# FPGA_Configuration.net
KiCad netlist of a schematic drawn in Altium Designer
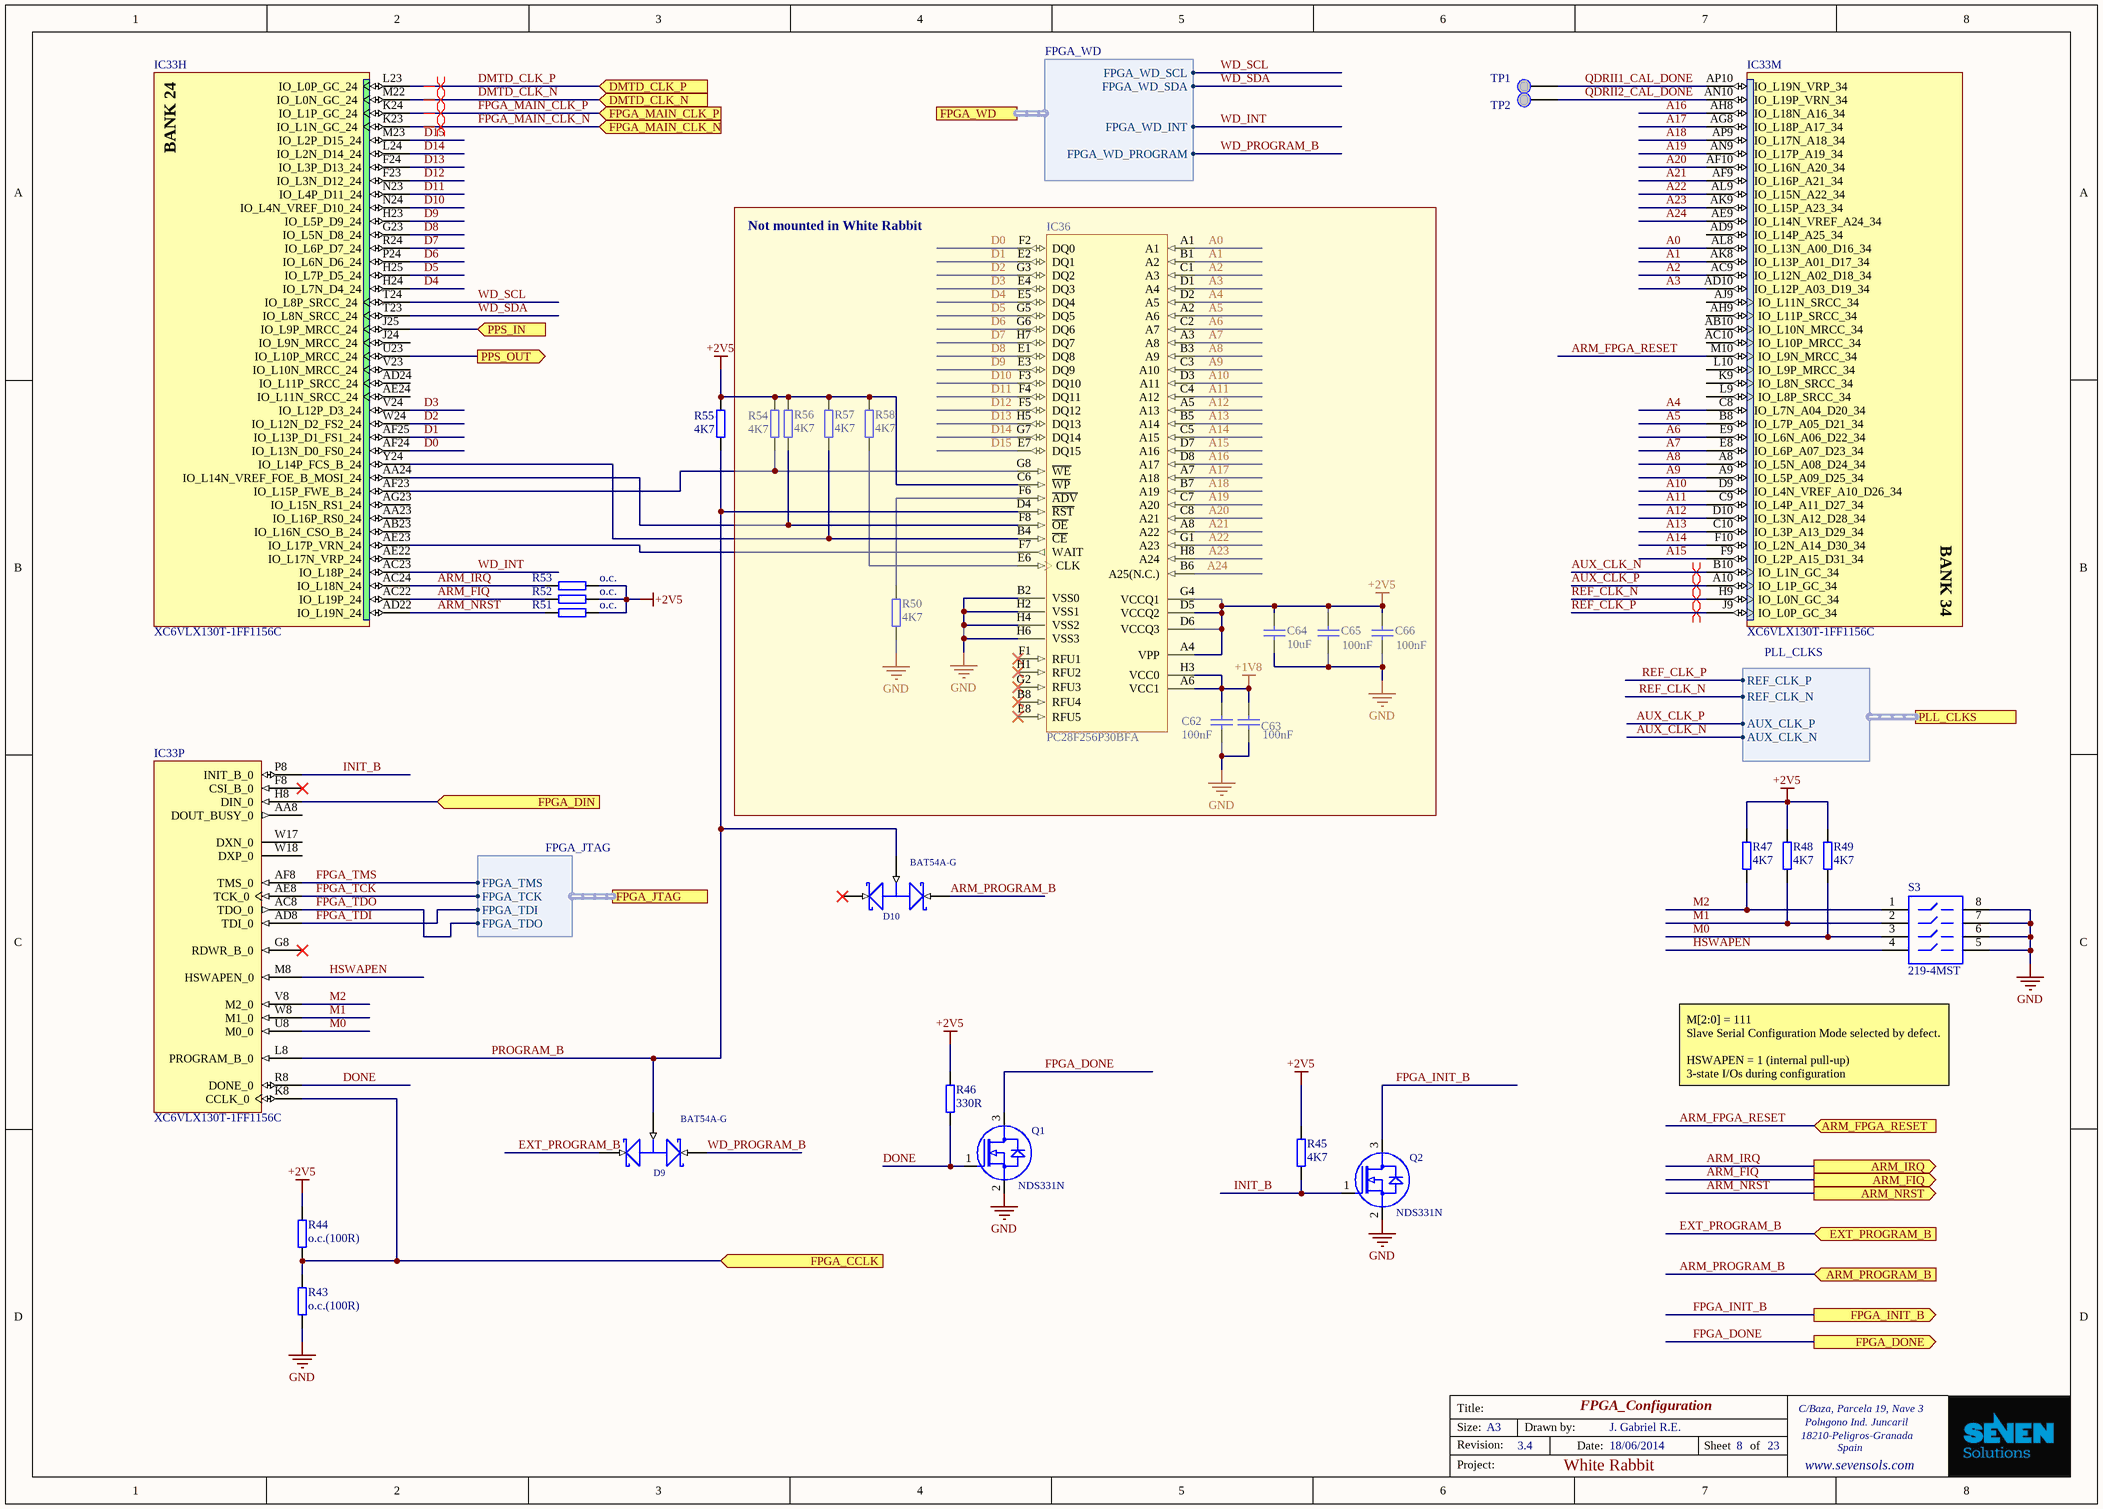
[diagram p0: FPGA_Configuration.SchDoc]

(export (version "E")
  (design (tool "Eeschema 10.0.6"))
  (components
    (comp (ref "C62")
      (value "100nF")
      (footprint "CC1005-0402")
      (description "Capacitor")
      (fields
        (field (name "TOLERANCE") "±10%")
        (field (name "VOLTAGE") "16V")
        (field (name "PUBLISHER") "Altium Limited")
      )
      (libsource (lib "wr_switch") (part "Cap"))
    )
    (comp (ref "C63")
      (value "100nF")
      (footprint "CC1005-0402")
      (description "Capacitor")
      (fields
        (field (name "TOLERANCE") "±10%")
        (field (name "VOLTAGE") "16V")
        (field (name "PUBLISHER") "Altium Limited")
      )
      (libsource (lib "wr_switch") (part "Cap"))
    )
    (comp (ref "C64")
      (value "10uF")
      (footprint "CC1608-0603")
      (description "Capacitor")
      (fields
        (field (name "TOLERANCE") "±20%")
        (field (name "VOLTAGE") "6.3V")
        (field (name "PUBLISHER") "Altium Limited")
      )
      (libsource (lib "wr_switch") (part "Cap"))
    )
    (comp (ref "C65")
      (value "100nF")
      (footprint "CC1005-0402")
      (description "Capacitor")
      (fields
        (field (name "TOLERANCE") "±10%")
        (field (name "VOLTAGE") "16V")
        (field (name "PUBLISHER") "Altium Limited")
      )
      (libsource (lib "wr_switch") (part "Cap"))
    )
    (comp (ref "C66")
      (value "100nF")
      (footprint "CC1005-0402")
      (description "Capacitor")
      (fields
        (field (name "TOLERANCE") "±10%")
        (field (name "VOLTAGE") "16V")
        (field (name "PUBLISHER") "Altium Limited")
      )
      (libsource (lib "wr_switch") (part "Cap"))
    )
    (comp (ref "D9")
      (value "BAT54A-G")
      (footprint "SOT23")
      (description "Schottky Barrier Double Diode")
      (fields (field (name "PUBLISHER") "Altium Limited"))
      (libsource (lib "wr_switch") (part "BAT54A.1"))
    )
    (comp (ref "D10")
      (value "BAT54A-G")
      (footprint "SOT23")
      (description "Schottky Barrier Double Diode")
      (fields (field (name "PUBLISHER") "Altium Limited"))
      (libsource (lib "wr_switch") (part "BAT54A.1"))
    )
    (comp (ref "IC33")
      (value "XC6VLX130T-1FF1156C")
      (footprint "FF1156")
      (fields (field (name "PUBLISHER") "Altium Limited"))
      (libsource (lib "") (part "XC6VLX130T-1FF1156C_1"))
    )
    (comp (ref "IC36")
      (value "PC28F256P30BFA")
      (footprint "BGA64C100P8X8_1300X1000X120")
      (description "NOR Flash Memory, 256Mbit")
      (libsource (lib "wr_switch") (part "PC28F256P30BFA"))
    )
    (comp (ref "Q1")
      (value "NDS331N")
      (footprint "SOT23-3")
      (description "N-Channel Logic Level Enhancement Mode Field Effect Transistor")
      (libsource (lib "wr_switch") (part "NDS331N"))
    )
    (comp (ref "Q2")
      (value "NDS331N")
      (footprint "SOT23-3")
      (description "N-Channel Logic Level Enhancement Mode Field Effect Transistor")
      (libsource (lib "wr_switch") (part "NDS331N"))
    )
    (comp (ref "R43")
      (value "o.c.(100R)")
      (footprint "0402")
      (description "SMD Resistor")
      (fields (field (name "TOLERANCE") "±1%") (field (name "Comment") "100R(o.c.)"))
      (libsource (lib "wr_switch") (part "RES_SMD"))
    )
    (comp (ref "R44")
      (value "o.c.(100R)")
      (footprint "0402")
      (description "SMD Resistor")
      (fields (field (name "TOLERANCE") "±1%") (field (name "Comment") "100R(o.c.)"))
      (libsource (lib "wr_switch") (part "RES_SMD"))
    )
    (comp (ref "R45")
      (value "4K7")
      (footprint "0402")
      (description "SMD Resistor")
      (fields (field (name "TOLERANCE") "±1%"))
      (libsource (lib "wr_switch") (part "RES_SMD"))
    )
    (comp (ref "R46")
      (value "330R")
      (footprint "0402")
      (description "SMD Resistor")
      (fields (field (name "TOLERANCE") "±1%"))
      (libsource (lib "wr_switch") (part "RES_SMD"))
    )
    (comp (ref "R47")
      (value "4K7")
      (footprint "0402")
      (description "SMD Resistor")
      (fields (field (name "TOLERANCE") "±1%"))
      (libsource (lib "wr_switch") (part "RES_SMD"))
    )
    (comp (ref "R48")
      (value "4K7")
      (footprint "0402")
      (description "SMD Resistor")
      (fields (field (name "TOLERANCE") "±1%"))
      (libsource (lib "wr_switch") (part "RES_SMD"))
    )
    (comp (ref "R49")
      (value "4K7")
      (footprint "0402")
      (description "SMD Resistor")
      (fields (field (name "TOLERANCE") "±1%"))
      (libsource (lib "wr_switch") (part "RES_SMD"))
    )
    (comp (ref "R50")
      (value "4K7")
      (footprint "0402")
      (description "SMD Resistor")
      (fields (field (name "TOLERANCE") "±1%"))
      (libsource (lib "wr_switch") (part "RES_SMD"))
    )
    (comp (ref "R51")
      (value "o.c.")
      (footprint "0402")
      (description "SMD Resistor")
      (libsource (lib "wr_switch") (part "RES_SMD"))
    )
    (comp (ref "R52")
      (value "o.c.")
      (footprint "0402")
      (description "SMD Resistor")
      (libsource (lib "wr_switch") (part "RES_SMD"))
    )
    (comp (ref "R53")
      (value "o.c.")
      (footprint "0402")
      (description "SMD Resistor")
      (libsource (lib "wr_switch") (part "RES_SMD"))
    )
    (comp (ref "R54")
      (value "4K7")
      (footprint "0402")
      (description "SMD Resistor")
      (fields (field (name "TOLERANCE") "±1%"))
      (libsource (lib "wr_switch") (part "RES_SMD"))
    )
    (comp (ref "R55")
      (value "4K7")
      (footprint "0402")
      (description "SMD Resistor")
      (fields (field (name "TOLERANCE") "±1%"))
      (libsource (lib "wr_switch") (part "RES_SMD"))
    )
    (comp (ref "R56")
      (value "4K7")
      (footprint "0402")
      (description "SMD Resistor")
      (fields (field (name "TOLERANCE") "±1%"))
      (libsource (lib "wr_switch") (part "RES_SMD"))
    )
    (comp (ref "R57")
      (value "4K7")
      (footprint "0402")
      (description "SMD Resistor")
      (fields (field (name "TOLERANCE") "±1%"))
      (libsource (lib "wr_switch") (part "RES_SMD"))
    )
    (comp (ref "R58")
      (value "4K7")
      (footprint "0402")
      (description "SMD Resistor")
      (fields (field (name "TOLERANCE") "±1%"))
      (libsource (lib "wr_switch") (part "RES_SMD"))
    )
    (comp (ref "S3")
      (value "219-4MST")
      (footprint "7S_WR:NHDS-8")
      (description "4 Positions DIP SWITCH")
      (fields (field (name "MANUFACTURER") "CTS Electrocomponents"))
      (libsource (lib "wr_switch") (part "SW-DIP4"))
    )
    (comp (ref "TP1")
      (value "Test Point")
      (footprint "TEST_PAD_1mm")
      (description "SMD 1mm Test Point")
      (libsource (lib "wr_switch") (part "TEST_POINT"))
    )
    (comp (ref "TP2")
      (value "Test Point")
      (footprint "TEST_PAD_1mm")
      (description "SMD 1mm Test Point")
      (libsource (lib "wr_switch") (part "TEST_POINT"))
    )
  )
  (nets
    (net (code "4") (name "+1V8") (class "Default")
      (node (ref "C62") (pin "2") (pinfunction "2_2") (pintype "passive"))
      (node (ref "C63") (pin "2") (pinfunction "2_2") (pintype "passive"))
      (node (ref "IC36") (pin "A6") (pinfunction "VCC1_A6") (pintype "power_in"))
      (node (ref "IC36") (pin "H3") (pinfunction "VCC0_H3") (pintype "power_in"))
    )
    (net (code "5") (name "+2V5") (class "Default")
      (node (ref "C64") (pin "2") (pinfunction "2_2") (pintype "passive"))
      (node (ref "C65") (pin "2") (pinfunction "2_2") (pintype "passive"))
      (node (ref "C66") (pin "2") (pinfunction "2_2") (pintype "passive"))
      (node (ref "IC36") (pin "A4") (pinfunction "VPP_A4") (pintype "passive"))
      (node (ref "IC36") (pin "C6") (pinfunction "~{WP}_C6") (pintype "input"))
      (node (ref "IC36") (pin "D5") (pinfunction "VCCQ2_D5") (pintype "power_in"))
      (node (ref "IC36") (pin "D6") (pinfunction "VCCQ3_D6") (pintype "power_in"))
      (node (ref "IC36") (pin "G4") (pinfunction "VCCQ1_G4") (pintype "power_in"))
      (node (ref "R44") (pin "2") (pinfunction "2_2") (pintype "passive"))
      (node (ref "R45") (pin "1") (pinfunction "1_1") (pintype "passive"))
      (node (ref "R46") (pin "2") (pinfunction "2_2") (pintype "passive"))
      (node (ref "R47") (pin "2") (pinfunction "2_2") (pintype "passive"))
      (node (ref "R48") (pin "2") (pinfunction "2_2") (pintype "passive"))
      (node (ref "R49") (pin "2") (pinfunction "2_2") (pintype "passive"))
      (node (ref "R51") (pin "1") (pinfunction "1_1") (pintype "passive"))
      (node (ref "R52") (pin "1") (pinfunction "1_1") (pintype "passive"))
      (node (ref "R53") (pin "1") (pinfunction "1_1") (pintype "passive"))
      (node (ref "R54") (pin "2") (pinfunction "2_2") (pintype "passive"))
      (node (ref "R55") (pin "2") (pinfunction "2_2") (pintype "passive"))
      (node (ref "R56") (pin "2") (pinfunction "2_2") (pintype "passive"))
      (node (ref "R57") (pin "2") (pinfunction "2_2") (pintype "passive"))
      (node (ref "R58") (pin "2") (pinfunction "2_2") (pintype "passive"))
    )
    (net (code "6") (name "/A0") (class "Default")
      (node (ref "IC33") (pin "AL8") (pinfunction "IO_L13N_A00_D16_34_AL8") (pintype "bidirectional"))
      (node (ref "IC36") (pin "A1") (pinfunction "A1_A1") (pintype "input"))
    )
    (net (code "7") (name "/A1") (class "Default")
      (node (ref "IC33") (pin "AK8") (pinfunction "IO_L13P_A01_D17_34_AK8") (pintype "bidirectional"))
      (node (ref "IC36") (pin "B1") (pinfunction "A2_B1") (pintype "input"))
    )
    (net (code "8") (name "/A2") (class "Default")
      (node (ref "IC33") (pin "AC9") (pinfunction "IO_L12N_A02_D18_34_AC9") (pintype "bidirectional"))
      (node (ref "IC36") (pin "C1") (pinfunction "A3_C1") (pintype "input"))
    )
    (net (code "9") (name "/A3") (class "Default")
      (node (ref "IC33") (pin "AD10") (pinfunction "IO_L12P_A03_D19_34_AD10") (pintype "bidirectional"))
      (node (ref "IC36") (pin "D1") (pinfunction "A4_D1") (pintype "input"))
    )
    (net (code "10") (name "/A4") (class "Default")
      (node (ref "IC33") (pin "C8") (pinfunction "IO_L7N_A04_D20_34_C8") (pintype "bidirectional"))
      (node (ref "IC36") (pin "D2") (pinfunction "A5_D2") (pintype "input"))
    )
    (net (code "11") (name "/A5") (class "Default")
      (node (ref "IC33") (pin "B8") (pinfunction "IO_L7P_A05_D21_34_B8") (pintype "bidirectional"))
      (node (ref "IC36") (pin "A2") (pinfunction "A6_A2") (pintype "input"))
    )
    (net (code "12") (name "/A6") (class "Default")
      (node (ref "IC33") (pin "E9") (pinfunction "IO_L6N_A06_D22_34_E9") (pintype "bidirectional"))
      (node (ref "IC36") (pin "C2") (pinfunction "A7_C2") (pintype "input"))
    )
    (net (code "13") (name "/A7") (class "Default")
      (node (ref "IC33") (pin "E8") (pinfunction "IO_L6P_A07_D23_34_E8") (pintype "bidirectional"))
      (node (ref "IC36") (pin "A3") (pinfunction "A8_A3") (pintype "input"))
    )
    (net (code "14") (name "/A8") (class "Default")
      (node (ref "IC33") (pin "A8") (pinfunction "IO_L5N_A08_D24_34_A8") (pintype "bidirectional"))
      (node (ref "IC36") (pin "B3") (pinfunction "A9_B3") (pintype "input"))
    )
    (net (code "15") (name "/A9") (class "Default")
      (node (ref "IC33") (pin "A9") (pinfunction "IO_L5P_A09_D25_34_A9") (pintype "bidirectional"))
      (node (ref "IC36") (pin "C3") (pinfunction "A10_C3") (pintype "input"))
    )
    (net (code "16") (name "/A10") (class "Default")
      (node (ref "IC33") (pin "D9") (pinfunction "IO_L4N_VREF_A10_D26_34_D9") (pintype "bidirectional"))
      (node (ref "IC36") (pin "D3") (pinfunction "A11_D3") (pintype "input"))
    )
    (net (code "17") (name "/A11") (class "Default")
      (node (ref "IC33") (pin "C9") (pinfunction "IO_L4P_A11_D27_34_C9") (pintype "bidirectional"))
      (node (ref "IC36") (pin "C4") (pinfunction "A12_C4") (pintype "input"))
    )
    (net (code "18") (name "/A12") (class "Default")
      (node (ref "IC33") (pin "D10") (pinfunction "IO_L3N_A12_D28_34_D10") (pintype "bidirectional"))
      (node (ref "IC36") (pin "A5") (pinfunction "A13_A5") (pintype "input"))
    )
    (net (code "19") (name "/A13") (class "Default")
      (node (ref "IC33") (pin "C10") (pinfunction "IO_L3P_A13_D29_34_C10") (pintype "bidirectional"))
      (node (ref "IC36") (pin "B5") (pinfunction "A14_B5") (pintype "input"))
    )
    (net (code "20") (name "/A14") (class "Default")
      (node (ref "IC33") (pin "F10") (pinfunction "IO_L2N_A14_D30_34_F10") (pintype "bidirectional"))
      (node (ref "IC36") (pin "C5") (pinfunction "A15_C5") (pintype "input"))
    )
    (net (code "21") (name "/A15") (class "Default")
      (node (ref "IC33") (pin "F9") (pinfunction "IO_L2P_A15_D31_34_F9") (pintype "bidirectional"))
      (node (ref "IC36") (pin "D7") (pinfunction "A16_D7") (pintype "input"))
    )
    (net (code "22") (name "/A16") (class "Default")
      (node (ref "IC33") (pin "AH8") (pinfunction "IO_L18N_A16_34_AH8") (pintype "bidirectional"))
      (node (ref "IC36") (pin "D8") (pinfunction "A17_D8") (pintype "input"))
    )
    (net (code "23") (name "/A17") (class "Default")
      (node (ref "IC33") (pin "AG8") (pinfunction "IO_L18P_A17_34_AG8") (pintype "bidirectional"))
      (node (ref "IC36") (pin "A7") (pinfunction "A18_A7") (pintype "input"))
    )
    (net (code "24") (name "/A18") (class "Default")
      (node (ref "IC33") (pin "AP9") (pinfunction "IO_L17N_A18_34_AP9") (pintype "bidirectional"))
      (node (ref "IC36") (pin "B7") (pinfunction "A19_B7") (pintype "input"))
    )
    (net (code "25") (name "/A19") (class "Default")
      (node (ref "IC33") (pin "AN9") (pinfunction "IO_L17P_A19_34_AN9") (pintype "bidirectional"))
      (node (ref "IC36") (pin "C7") (pinfunction "A20_C7") (pintype "input"))
    )
    (net (code "26") (name "/A20") (class "Default")
      (node (ref "IC33") (pin "AF10") (pinfunction "IO_L16N_A20_34_AF10") (pintype "bidirectional"))
      (node (ref "IC36") (pin "C8") (pinfunction "A21_C8") (pintype "input"))
    )
    (net (code "27") (name "/A21") (class "Default")
      (node (ref "IC33") (pin "AF9") (pinfunction "IO_L16P_A21_34_AF9") (pintype "bidirectional"))
      (node (ref "IC36") (pin "A8") (pinfunction "A22_A8") (pintype "input"))
    )
    (net (code "28") (name "/A22") (class "Default")
      (node (ref "IC33") (pin "AL9") (pinfunction "IO_L15N_A22_34_AL9") (pintype "bidirectional"))
      (node (ref "IC36") (pin "G1") (pinfunction "A23_G1") (pintype "input"))
    )
    (net (code "29") (name "/A23") (class "Default")
      (node (ref "IC33") (pin "AK9") (pinfunction "IO_L15P_A23_34_AK9") (pintype "bidirectional"))
      (node (ref "IC36") (pin "H8") (pinfunction "A24_H8") (pintype "input"))
    )
    (net (code "30") (name "/A24") (class "Default")
      (node (ref "IC33") (pin "AE9") (pinfunction "IO_L14N_VREF_A24_34_AE9") (pintype "bidirectional"))
      (node (ref "IC36") (pin "B6") (pinfunction "A25(N.C.)_B6") (pintype "input"))
    )
    (net (code "31") (name "/ARM_FIQ") (class "Default")
      (node (ref "IC33") (pin "AC22") (pinfunction "IO_L19P_24_AC22") (pintype "bidirectional"))
      (node (ref "R52") (pin "2") (pinfunction "2_2") (pintype "passive"))
    )
    (net (code "32") (name "/ARM_FPGA_RESET") (class "Default")
      (node (ref "IC33") (pin "M10") (pinfunction "IO_L9N_MRCC_34_M10") (pintype "bidirectional"))
    )
    (net (code "33") (name "/ARM_IRQ") (class "Default")
      (node (ref "IC33") (pin "AC24") (pinfunction "IO_L18N_24_AC24") (pintype "bidirectional"))
      (node (ref "R53") (pin "2") (pinfunction "2_2") (pintype "passive"))
    )
    (net (code "34") (name "/ARM_NRST") (class "Default")
      (node (ref "IC33") (pin "AD22") (pinfunction "IO_L19N_24_AD22") (pintype "bidirectional"))
      (node (ref "R51") (pin "2") (pinfunction "2_2") (pintype "passive"))
    )
    (net (code "35") (name "/ARM_PROGRAM_B") (class "Default")
      (node (ref "D10") (pin "2") (pinfunction "K2_2") (pintype "input"))
    )
    (net (code "36") (name "/AUX_CLK_N") (class "Default")
      (node (ref "IC33") (pin "B10") (pinfunction "IO_L1N_GC_34_B10") (pintype "bidirectional"))
    )
    (net (code "37") (name "/AUX_CLK_P") (class "Default")
      (node (ref "IC33") (pin "A10") (pinfunction "IO_L1P_GC_34_A10") (pintype "bidirectional"))
    )
    (net (code "38") (name "/D0") (class "Default")
      (node (ref "IC33") (pin "AF24") (pinfunction "IO_L13N_D0_FS0_24_AF24") (pintype "bidirectional"))
      (node (ref "IC36") (pin "F2") (pinfunction "DQ0_F2") (pintype "bidirectional"))
    )
    (net (code "39") (name "/D1") (class "Default")
      (node (ref "IC33") (pin "AF25") (pinfunction "IO_L13P_D1_FS1_24_AF25") (pintype "bidirectional"))
      (node (ref "IC36") (pin "E2") (pinfunction "DQ1_E2") (pintype "bidirectional"))
    )
    (net (code "40") (name "/D2") (class "Default")
      (node (ref "IC33") (pin "W24") (pinfunction "IO_L12N_D2_FS2_24_W24") (pintype "bidirectional"))
      (node (ref "IC36") (pin "G3") (pinfunction "DQ2_G3") (pintype "bidirectional"))
    )
    (net (code "41") (name "/D3") (class "Default")
      (node (ref "IC33") (pin "V24") (pinfunction "IO_L12P_D3_24_V24") (pintype "bidirectional"))
      (node (ref "IC36") (pin "E4") (pinfunction "DQ3_E4") (pintype "bidirectional"))
    )
    (net (code "42") (name "/D4") (class "Default")
      (node (ref "IC33") (pin "H24") (pinfunction "IO_L7N_D4_24_H24") (pintype "bidirectional"))
      (node (ref "IC36") (pin "E5") (pinfunction "DQ4_E5") (pintype "bidirectional"))
    )
    (net (code "43") (name "/D5") (class "Default")
      (node (ref "IC33") (pin "H25") (pinfunction "IO_L7P_D5_24_H25") (pintype "bidirectional"))
      (node (ref "IC36") (pin "G5") (pinfunction "DQ5_G5") (pintype "bidirectional"))
    )
    (net (code "44") (name "/D6") (class "Default")
      (node (ref "IC33") (pin "P24") (pinfunction "IO_L6N_D6_24_P24") (pintype "bidirectional"))
      (node (ref "IC36") (pin "G6") (pinfunction "DQ6_G6") (pintype "bidirectional"))
    )
    (net (code "45") (name "/D7") (class "Default")
      (node (ref "IC33") (pin "R24") (pinfunction "IO_L6P_D7_24_R24") (pintype "bidirectional"))
      (node (ref "IC36") (pin "H7") (pinfunction "DQ7_H7") (pintype "bidirectional"))
    )
    (net (code "46") (name "/D8") (class "Default")
      (node (ref "IC33") (pin "G23") (pinfunction "IO_L5N_D8_24_G23") (pintype "bidirectional"))
      (node (ref "IC36") (pin "E1") (pinfunction "DQ8_E1") (pintype "bidirectional"))
    )
    (net (code "47") (name "/D9") (class "Default")
      (node (ref "IC33") (pin "H23") (pinfunction "IO_L5P_D9_24_H23") (pintype "bidirectional"))
      (node (ref "IC36") (pin "E3") (pinfunction "DQ9_E3") (pintype "bidirectional"))
    )
    (net (code "48") (name "/D10") (class "Default")
      (node (ref "IC33") (pin "N24") (pinfunction "IO_L4N_VREF_D10_24_N24") (pintype "bidirectional"))
      (node (ref "IC36") (pin "F3") (pinfunction "DQ10_F3") (pintype "bidirectional"))
    )
    (net (code "49") (name "/D11") (class "Default")
      (node (ref "IC33") (pin "N23") (pinfunction "IO_L4P_D11_24_N23") (pintype "bidirectional"))
      (node (ref "IC36") (pin "F4") (pinfunction "DQ11_F4") (pintype "bidirectional"))
    )
    (net (code "50") (name "/D12") (class "Default")
      (node (ref "IC33") (pin "F23") (pinfunction "IO_L3N_D12_24_F23") (pintype "bidirectional"))
      (node (ref "IC36") (pin "F5") (pinfunction "DQ12_F5") (pintype "bidirectional"))
    )
    (net (code "51") (name "/D13") (class "Default")
      (node (ref "IC33") (pin "F24") (pinfunction "IO_L3P_D13_24_F24") (pintype "bidirectional"))
      (node (ref "IC36") (pin "H5") (pinfunction "DQ13_H5") (pintype "bidirectional"))
    )
    (net (code "52") (name "/D14") (class "Default")
      (node (ref "IC33") (pin "L24") (pinfunction "IO_L2N_D14_24_L24") (pintype "bidirectional"))
      (node (ref "IC36") (pin "G7") (pinfunction "DQ14_G7") (pintype "bidirectional"))
    )
    (net (code "53") (name "/D15") (class "Default")
      (node (ref "IC33") (pin "M23") (pinfunction "IO_L2P_D15_24_M23") (pintype "bidirectional"))
      (node (ref "IC36") (pin "E7") (pinfunction "DQ15_E7") (pintype "bidirectional"))
    )
    (net (code "54") (name "/DMTD_CLK_N") (class "Default")
      (node (ref "IC33") (pin "M22") (pinfunction "IO_L0N_GC_24_M22") (pintype "bidirectional"))
    )
    (net (code "55") (name "/DMTD_CLK_P") (class "Default")
      (node (ref "IC33") (pin "L23") (pinfunction "IO_L0P_GC_24_L23") (pintype "bidirectional"))
    )
    (net (code "56") (name "/DONE") (class "Default")
      (node (ref "IC33") (pin "R8") (pinfunction "DONE_0_R8") (pintype "bidirectional"))
      (node (ref "Q1") (pin "1") (pinfunction "GATE_1") (pintype "passive"))
      (node (ref "R46") (pin "1") (pinfunction "1_1") (pintype "passive"))
    )
    (net (code "57") (name "/EXT_PROGRAM_B") (class "Default")
      (node (ref "D9") (pin "1") (pinfunction "K1_1") (pintype "input"))
    )
    (net (code "58") (name "/FPGA_CCLK") (class "Default")
      (node (ref "IC33") (pin "K8") (pinfunction "CCLK_0_K8") (pintype "bidirectional"))
      (node (ref "R43") (pin "2") (pinfunction "2_2") (pintype "passive"))
      (node (ref "R44") (pin "1") (pinfunction "1_1") (pintype "passive"))
    )
    (net (code "59") (name "/FPGA_DIN") (class "Default")
      (node (ref "IC33") (pin "H8") (pinfunction "DIN_0_H8") (pintype "input"))
    )
    (net (code "60") (name "/FPGA_DONE") (class "Default")
      (node (ref "Q1") (pin "3") (pinfunction "DRAIN_3") (pintype "passive"))
    )
    (net (code "61") (name "/FPGA_INIT_B") (class "Default")
      (node (ref "Q2") (pin "3") (pinfunction "DRAIN_3") (pintype "passive"))
    )
    (net (code "62") (name "/FPGA_MAIN_CLK_N") (class "Default")
      (node (ref "IC33") (pin "K23") (pinfunction "IO_L1N_GC_24_K23") (pintype "bidirectional"))
    )
    (net (code "63") (name "/FPGA_MAIN_CLK_P") (class "Default")
      (node (ref "IC33") (pin "K24") (pinfunction "IO_L1P_GC_24_K24") (pintype "bidirectional"))
    )
    (net (code "64") (name "/FPGA_TCK") (class "Default")
      (node (ref "IC33") (pin "AE8") (pinfunction "TCK_0_AE8") (pintype "input"))
    )
    (net (code "65") (name "/FPGA_TDI") (class "Default")
      (node (ref "IC33") (pin "AD8") (pinfunction "TDI_0_AD8") (pintype "input"))
    )
    (net (code "66") (name "/FPGA_TDO") (class "Default")
      (node (ref "IC33") (pin "AC8") (pinfunction "TDO_0_AC8") (pintype "output"))
    )
    (net (code "67") (name "/FPGA_TMS") (class "Default")
      (node (ref "IC33") (pin "AF8") (pinfunction "TMS_0_AF8") (pintype "input"))
    )
    (net (code "68") (name "/HSWAPEN") (class "Default")
      (node (ref "IC33") (pin "M8") (pinfunction "HSWAPEN_0_M8") (pintype "input"))
      (node (ref "S3") (pin "4") (pinfunction "4_4") (pintype "passive"))
    )
    (net (code "69") (name "/INIT_B") (class "Default")
      (node (ref "IC33") (pin "P8") (pinfunction "INIT_B_0_P8") (pintype "bidirectional"))
      (node (ref "Q2") (pin "1") (pinfunction "GATE_1") (pintype "passive"))
      (node (ref "R45") (pin "2") (pinfunction "2_2") (pintype "passive"))
    )
    (net (code "70") (name "/M0") (class "Default")
      (node (ref "IC33") (pin "U8") (pinfunction "M0_0_U8") (pintype "input"))
      (node (ref "R49") (pin "1") (pinfunction "1_1") (pintype "passive"))
      (node (ref "S3") (pin "3") (pinfunction "3_3") (pintype "passive"))
    )
    (net (code "71") (name "/M1") (class "Default")
      (node (ref "IC33") (pin "W8") (pinfunction "M1_0_W8") (pintype "input"))
      (node (ref "R48") (pin "1") (pinfunction "1_1") (pintype "passive"))
      (node (ref "S3") (pin "2") (pinfunction "2_2") (pintype "passive"))
    )
    (net (code "72") (name "/M2") (class "Default")
      (node (ref "IC33") (pin "V8") (pinfunction "M2_0_V8") (pintype "input"))
      (node (ref "R47") (pin "1") (pinfunction "1_1") (pintype "passive"))
      (node (ref "S3") (pin "1") (pinfunction "1_1") (pintype "passive"))
    )
    (net (code "73") (name "/PPS_IN") (class "Default")
      (node (ref "IC33") (pin "J25") (pinfunction "IO_L9P_MRCC_24_J25") (pintype "bidirectional"))
    )
    (net (code "74") (name "/PPS_OUT") (class "Default")
      (node (ref "IC33") (pin "U23") (pinfunction "IO_L10P_MRCC_24_U23") (pintype "bidirectional"))
    )
    (net (code "75") (name "/PROGRAM_B") (class "Default")
      (node (ref "D10") (pin "3") (pinfunction "A_3") (pintype "input"))
      (node (ref "D9") (pin "3") (pinfunction "A_3") (pintype "input"))
      (node (ref "IC33") (pin "L8") (pinfunction "PROGRAM_B_0_L8") (pintype "input"))
      (node (ref "IC36") (pin "D4") (pinfunction "~{RST}_D4") (pintype "input"))
      (node (ref "R55") (pin "1") (pinfunction "1_1") (pintype "passive"))
    )
    (net (code "76") (name "/QDRII1_CAL_DONE") (class "Default")
      (node (ref "IC33") (pin "AP10") (pinfunction "IO_L19N_VRP_34_AP10") (pintype "bidirectional"))
      (node (ref "TP1") (pin "1") (pinfunction "TP_1") (pintype "passive"))
    )
    (net (code "77") (name "/QDRII2_CAL_DONE") (class "Default")
      (node (ref "IC33") (pin "AN10") (pinfunction "IO_L19P_VRN_34_AN10") (pintype "bidirectional"))
      (node (ref "TP2") (pin "1") (pinfunction "TP_1") (pintype "passive"))
    )
    (net (code "78") (name "/REF_CLK_N") (class "Default")
      (node (ref "IC33") (pin "H9") (pinfunction "IO_L0N_GC_34_H9") (pintype "bidirectional"))
    )
    (net (code "79") (name "/REF_CLK_P") (class "Default")
      (node (ref "IC33") (pin "J9") (pinfunction "IO_L0P_GC_34_J9") (pintype "bidirectional"))
    )
    (net (code "80") (name "/WD_INT") (class "Default")
      (node (ref "IC33") (pin "AC23") (pinfunction "IO_L18P_24_AC23") (pintype "bidirectional"))
    )
    (net (code "81") (name "/WD_PROGRAM_B") (class "Default")
      (node (ref "D9") (pin "2") (pinfunction "K2_2") (pintype "input"))
    )
    (net (code "82") (name "/WD_SCL") (class "Default")
      (node (ref "IC33") (pin "T24") (pinfunction "IO_L8P_SRCC_24_T24") (pintype "bidirectional"))
    )
    (net (code "83") (name "/WD_SDA") (class "Default")
      (node (ref "IC33") (pin "T23") (pinfunction "IO_L8N_SRCC_24_T23") (pintype "bidirectional"))
    )
    (net (code "87") (name "GND") (class "Default")
      (node (ref "C62") (pin "1") (pinfunction "1_1") (pintype "passive"))
      (node (ref "C63") (pin "1") (pinfunction "1_1") (pintype "passive"))
      (node (ref "C64") (pin "1") (pinfunction "1_1") (pintype "passive"))
      (node (ref "C65") (pin "1") (pinfunction "1_1") (pintype "passive"))
      (node (ref "C66") (pin "1") (pinfunction "1_1") (pintype "passive"))
      (node (ref "IC36") (pin "B2") (pinfunction "VSS0_B2") (pintype "power_in"))
      (node (ref "IC36") (pin "H2") (pinfunction "VSS1_H2") (pintype "power_in"))
      (node (ref "IC36") (pin "H4") (pinfunction "VSS2_H4") (pintype "power_in"))
      (node (ref "IC36") (pin "H6") (pinfunction "VSS3_H6") (pintype "power_in"))
      (node (ref "Q1") (pin "2") (pinfunction "SOURCE_2") (pintype "passive"))
      (node (ref "Q2") (pin "2") (pinfunction "SOURCE_2") (pintype "passive"))
      (node (ref "R43") (pin "1") (pinfunction "1_1") (pintype "passive"))
      (node (ref "R50") (pin "1") (pinfunction "1_1") (pintype "passive"))
      (node (ref "S3") (pin "5") (pinfunction "5_5") (pintype "passive"))
      (node (ref "S3") (pin "6") (pinfunction "6_6") (pintype "passive"))
      (node (ref "S3") (pin "7") (pinfunction "7_7") (pintype "passive"))
      (node (ref "S3") (pin "8") (pinfunction "8_8") (pintype "passive"))
    )
    (net (code "88") (name "Net-(IC33H-IO_L14N_VREF_FOE_B_MOSI_24)") (class "Default")
      (node (ref "IC33") (pin "AA24") (pinfunction "IO_L14N_VREF_FOE_B_MOSI_24_AA24") (pintype "bidirectional"))
      (node (ref "IC36") (pin "F8") (pinfunction "~{OE}_F8") (pintype "input"))
      (node (ref "R56") (pin "1") (pinfunction "1_1") (pintype "passive"))
    )
    (net (code "89") (name "Net-(IC33H-IO_L14P_FCS_B_24)") (class "Default")
      (node (ref "IC33") (pin "Y24") (pinfunction "IO_L14P_FCS_B_24_Y24") (pintype "bidirectional"))
      (node (ref "IC36") (pin "B4") (pinfunction "~{CE}_B4") (pintype "input"))
      (node (ref "R57") (pin "1") (pinfunction "1_1") (pintype "passive"))
    )
    (net (code "90") (name "Net-(IC33H-IO_L15P_FWE_B_24)") (class "Default")
      (node (ref "IC33") (pin "AF23") (pinfunction "IO_L15P_FWE_B_24_AF23") (pintype "bidirectional"))
      (node (ref "IC36") (pin "G8") (pinfunction "~{WE}_G8") (pintype "input"))
      (node (ref "R54") (pin "1") (pinfunction "1_1") (pintype "passive"))
    )
    (net (code "91") (name "Net-(IC33H-IO_L17P_VRN_24)") (class "Default")
      (node (ref "IC33") (pin "AE23") (pinfunction "IO_L17P_VRN_24_AE23") (pintype "bidirectional"))
      (node (ref "IC36") (pin "F7") (pinfunction "WAIT_F7") (pintype "output"))
    )
    (net (code "92") (name "Net-(IC36-CLK)") (class "Default")
      (node (ref "IC36") (pin "E6") (pinfunction "CLK_E6") (pintype "input"))
      (node (ref "R58") (pin "1") (pinfunction "1_1") (pintype "passive"))
    )
    (net (code "93") (name "Net-(IC36-~{ADV})") (class "Default")
      (node (ref "IC36") (pin "F6") (pinfunction "~{ADV}_F6") (pintype "input"))
      (node (ref "R50") (pin "2") (pinfunction "2_2") (pintype "passive"))
    )
    (net (code "94") (name "unconnected-(D10-K1-Pad1)") (class "Default")
      (node (ref "D10") (pin "1") (pinfunction "K1_1") (pintype "input+no_connect"))
    )
    (net (code "95") (name "unconnected-(IC33H-IO_L9N_MRCC_24-PadJ24)") (class "Default")
      (node (ref "IC33") (pin "J24") (pinfunction "IO_L9N_MRCC_24_J24") (pintype "bidirectional"))
    )
    (net (code "96") (name "unconnected-(IC33H-IO_L10N_MRCC_24-PadV23)") (class "Default")
      (node (ref "IC33") (pin "V23") (pinfunction "IO_L10N_MRCC_24_V23") (pintype "bidirectional"))
    )
    (net (code "97") (name "unconnected-(IC33H-IO_L11N_SRCC_24-PadAE24)") (class "Default")
      (node (ref "IC33") (pin "AE24") (pinfunction "IO_L11N_SRCC_24_AE24") (pintype "bidirectional"))
    )
    (net (code "98") (name "unconnected-(IC33H-IO_L11P_SRCC_24-PadAD24)") (class "Default")
      (node (ref "IC33") (pin "AD24") (pinfunction "IO_L11P_SRCC_24_AD24") (pintype "bidirectional"))
    )
    (net (code "99") (name "unconnected-(IC33H-IO_L15N_RS1_24-PadAG23)") (class "Default")
      (node (ref "IC33") (pin "AG23") (pinfunction "IO_L15N_RS1_24_AG23") (pintype "bidirectional"))
    )
    (net (code "100") (name "unconnected-(IC33H-IO_L16N_CSO_B_24-PadAB23)") (class "Default")
      (node (ref "IC33") (pin "AB23") (pinfunction "IO_L16N_CSO_B_24_AB23") (pintype "bidirectional"))
    )
    (net (code "101") (name "unconnected-(IC33H-IO_L16P_RS0_24-PadAA23)") (class "Default")
      (node (ref "IC33") (pin "AA23") (pinfunction "IO_L16P_RS0_24_AA23") (pintype "bidirectional"))
    )
    (net (code "102") (name "unconnected-(IC33H-IO_L17N_VRP_24-PadAE22)") (class "Default")
      (node (ref "IC33") (pin "AE22") (pinfunction "IO_L17N_VRP_24_AE22") (pintype "bidirectional"))
    )
    (net (code "103") (name "unconnected-(IC33M-IO_L8N_SRCC_34-PadK9)") (class "Default")
      (node (ref "IC33") (pin "K9") (pinfunction "IO_L8N_SRCC_34_K9") (pintype "bidirectional"))
    )
    (net (code "104") (name "unconnected-(IC33M-IO_L8P_SRCC_34-PadL9)") (class "Default")
      (node (ref "IC33") (pin "L9") (pinfunction "IO_L8P_SRCC_34_L9") (pintype "bidirectional"))
    )
    (net (code "105") (name "unconnected-(IC33M-IO_L9P_MRCC_34-PadL10)") (class "Default")
      (node (ref "IC33") (pin "L10") (pinfunction "IO_L9P_MRCC_34_L10") (pintype "bidirectional"))
    )
    (net (code "106") (name "unconnected-(IC33M-IO_L10N_MRCC_34-PadAB10)") (class "Default")
      (node (ref "IC33") (pin "AB10") (pinfunction "IO_L10N_MRCC_34_AB10") (pintype "bidirectional"))
    )
    (net (code "107") (name "unconnected-(IC33M-IO_L10P_MRCC_34-PadAC10)") (class "Default")
      (node (ref "IC33") (pin "AC10") (pinfunction "IO_L10P_MRCC_34_AC10") (pintype "bidirectional"))
    )
    (net (code "108") (name "unconnected-(IC33M-IO_L11N_SRCC_34-PadAJ9)") (class "Default")
      (node (ref "IC33") (pin "AJ9") (pinfunction "IO_L11N_SRCC_34_AJ9") (pintype "bidirectional"))
    )
    (net (code "109") (name "unconnected-(IC33M-IO_L11P_SRCC_34-PadAH9)") (class "Default")
      (node (ref "IC33") (pin "AH9") (pinfunction "IO_L11P_SRCC_34_AH9") (pintype "bidirectional"))
    )
    (net (code "110") (name "unconnected-(IC33M-IO_L14P_A25_34-PadAD9)") (class "Default")
      (node (ref "IC33") (pin "AD9") (pinfunction "IO_L14P_A25_34_AD9") (pintype "bidirectional"))
    )
    (net (code "111") (name "unconnected-(IC33P-CSI_B_0-PadF8)") (class "Default")
      (node (ref "IC33") (pin "F8") (pinfunction "CSI_B_0_F8") (pintype "input+no_connect"))
    )
    (net (code "112") (name "unconnected-(IC33P-DOUT_BUSY_0-PadAA8)") (class "Default")
      (node (ref "IC33") (pin "AA8") (pinfunction "DOUT_BUSY_0_AA8") (pintype "output"))
    )
    (net (code "113") (name "unconnected-(IC33P-DXN_0-PadW17)") (class "Default")
      (node (ref "IC33") (pin "W17") (pinfunction "DXN_0_W17") (pintype "passive"))
    )
    (net (code "114") (name "unconnected-(IC33P-DXP_0-PadW18)") (class "Default")
      (node (ref "IC33") (pin "W18") (pinfunction "DXP_0_W18") (pintype "passive"))
    )
    (net (code "115") (name "unconnected-(IC33P-RDWR_B_0-PadG8)") (class "Default")
      (node (ref "IC33") (pin "G8") (pinfunction "RDWR_B_0_G8") (pintype "input+no_connect"))
    )
    (net (code "116") (name "unconnected-(IC36-RFU1-PadF1)") (class "Default")
      (node (ref "IC36") (pin "F1") (pinfunction "RFU1_F1") (pintype "input+no_connect"))
    )
    (net (code "117") (name "unconnected-(IC36-RFU2-PadH1)") (class "Default")
      (node (ref "IC36") (pin "H1") (pinfunction "RFU2_H1") (pintype "input+no_connect"))
    )
    (net (code "118") (name "unconnected-(IC36-RFU3-PadG2)") (class "Default")
      (node (ref "IC36") (pin "G2") (pinfunction "RFU3_G2") (pintype "input+no_connect"))
    )
    (net (code "119") (name "unconnected-(IC36-RFU4-PadB8)") (class "Default")
      (node (ref "IC36") (pin "B8") (pinfunction "RFU4_B8") (pintype "input+no_connect"))
    )
    (net (code "120") (name "unconnected-(IC36-RFU5-PadE8)") (class "Default")
      (node (ref "IC36") (pin "E8") (pinfunction "RFU5_E8") (pintype "input+no_connect"))
    )
  )
)
